# Sch_mcu_brd_mcu.net
KiCad netlist of a schematic drawn in Altium Designer
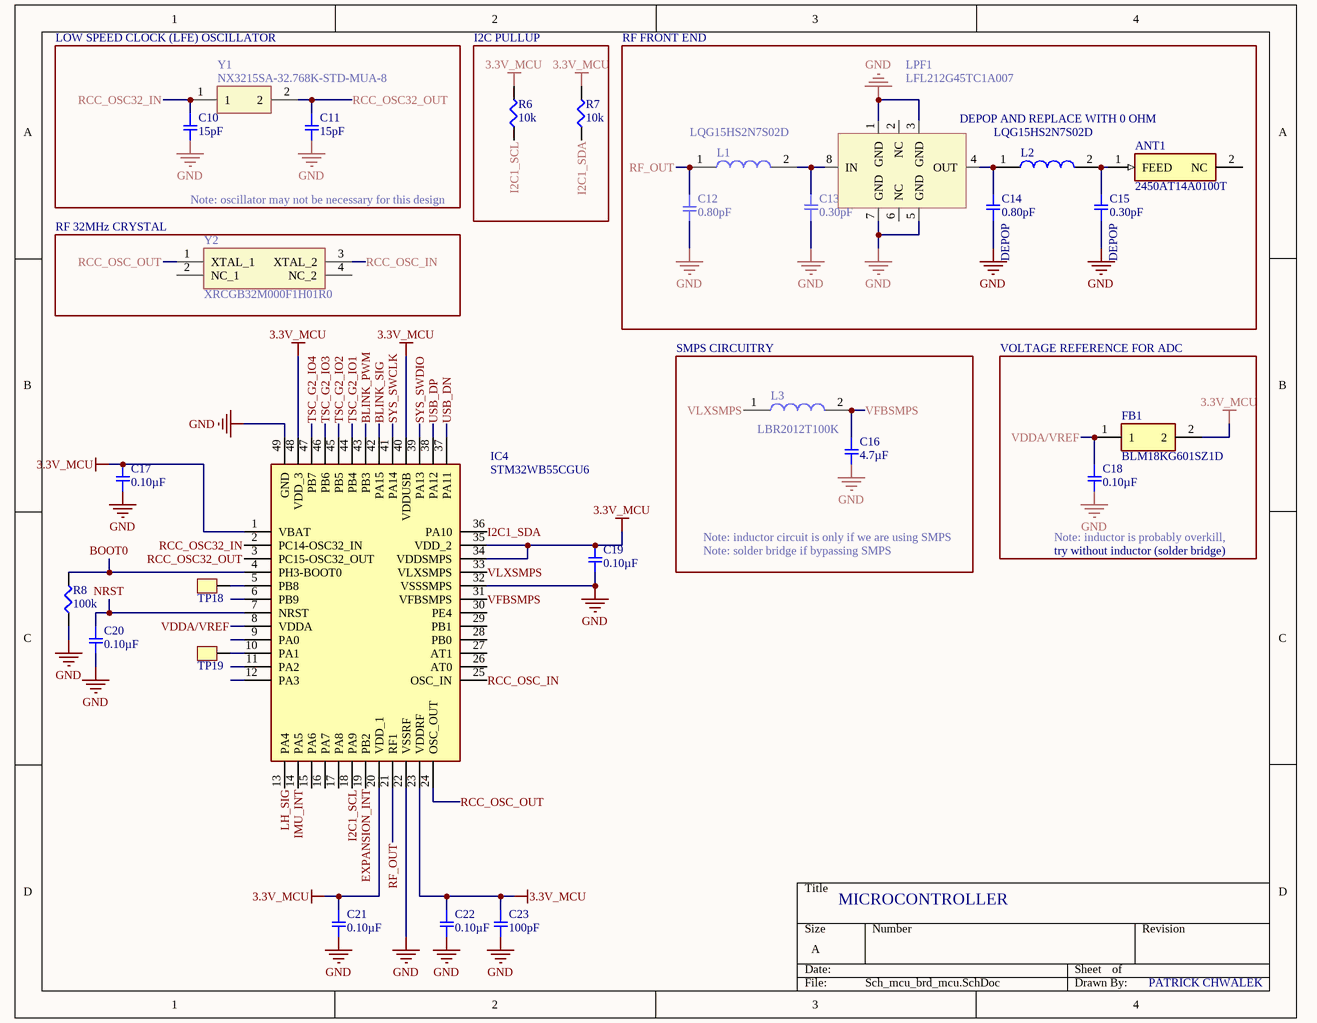
[diagram p0: Sch_mcu_brd_mcu.SchDoc]

(export (version "E")
  (design (tool "Eeschema 10.0.6"))
  (components
    (comp (ref "ANT1")
      (value "2450AT14A0100T")
      (footprint "SamacSys:ANTC1608X40N")
      (description "Antenna")
      (fields (field (name "MOUSER PART NUMBER") "609-2450AT14A0100T"))
      (libsource (lib "SamacSys") (part "2450AT14A0100T"))
    )
    (comp (ref "C10")
      (value "15pF")
      (footprint "SMD-0402C")
      (description "CAP CER 15PF 50V NP0 0402")
      (fields
        (field (name "DIGI-KEY PART NUMBER") "490-11147-1-ND")
        (field (name "PART NUMBER") "GCM1555C1H150JA16D")
      )
      (libsource (lib "capacitor_murata_0402") (part "GCM1555C1H150JA16D"))
    )
    (comp (ref "C11")
      (value "15pF")
      (footprint "SMD-0402C")
      (description "CAP CER 15PF 50V NP0 0402")
      (fields
        (field (name "DIGI-KEY PART NUMBER") "490-11147-1-ND")
        (field (name "PART NUMBER") "GCM1555C1H150JA16D")
      )
      (libsource (lib "capacitor_murata_0402") (part "GCM1555C1H150JA16D"))
    )
    (comp (ref "C12")
      (value "0.80pF")
      (footprint "SMD-0402C")
      (description "CAP CER 0.8PF 50V NP0 0402")
      (fields
        (field (name "DIGI-KEY PART NUMBER") "490-6269-1-ND")
        (field (name "PART NUMBER") "GRM1555C1HR80BA01D")
      )
      (libsource (lib "capacitor_murata_0402") (part "GRM1555C1HR80BA01D"))
    )
    (comp (ref "C13")
      (value "0.30pF")
      (footprint "SMD-0402C")
      (description "CAP CER 0.3PF 50V NP0 0402")
      (fields
        (field (name "DIGI-KEY PART NUMBER") "490-6261-1-ND")
        (field (name "PART NUMBER") "GRM1555C1HR30WA01D")
      )
      (libsource (lib "capacitor_murata_0402") (part "GRM1555C1HR30WA01D"))
    )
    (comp (ref "C14")
      (value "0.80pF")
      (footprint "SMD-0402C")
      (description "CAP CER 0.8PF 50V NP0 0402")
      (fields
        (field (name "DIGI-KEY PART NUMBER") "490-6269-1-ND")
        (field (name "PART NUMBER") "GRM1555C1HR80BA01D")
      )
      (libsource (lib "capacitor_murata_0402") (part "GRM1555C1HR80BA01D"))
    )
    (comp (ref "C15")
      (value "0.30pF")
      (footprint "SMD-0402C")
      (description "CAP CER 0.3PF 50V NP0 0402")
      (fields
        (field (name "DIGI-KEY PART NUMBER") "490-6261-1-ND")
        (field (name "PART NUMBER") "GRM1555C1HR30WA01D")
      )
      (libsource (lib "capacitor_murata_0402") (part "GRM1555C1HR30WA01D"))
    )
    (comp (ref "C16")
      (value "4.7µF")
      (footprint "SMD-0402C")
      (description "CAP CER 4.7UF 4V X5R 0402")
      (fields
        (field (name "DIGI-KEY PART NUMBER") "490-13231-1-ND")
        (field (name "PART NUMBER") "GRM153R60G475ME15D")
      )
      (libsource (lib "capacitor_murata_0402") (part "GRM153R60G475ME15D"))
    )
    (comp (ref "C17")
      (value "0.10µF")
      (footprint "SMD-0402C")
      (description "CAP CER 0.1UF 16V X7R 0402")
      (fields
        (field (name "DIGI-KEY PART NUMBER") "490-4759-1-ND")
        (field (name "PART NUMBER") "GCM155R71C104KA55D")
      )
      (libsource (lib "capacitor_murata_0402") (part "GCM155R71C104KA55D"))
    )
    (comp (ref "C18")
      (value "0.10µF")
      (footprint "SMD-0402C")
      (description "CAP CER 0.1UF 16V X7R 0402")
      (fields
        (field (name "DIGI-KEY PART NUMBER") "490-4759-1-ND")
        (field (name "PART NUMBER") "GCM155R71C104KA55D")
      )
      (libsource (lib "capacitor_murata_0402") (part "GCM155R71C104KA55D"))
    )
    (comp (ref "C19")
      (value "0.10µF")
      (footprint "SMD-0402C")
      (description "CAP CER 0.1UF 16V X7R 0402")
      (fields
        (field (name "DIGI-KEY PART NUMBER") "490-4759-1-ND")
        (field (name "PART NUMBER") "GCM155R71C104KA55D")
      )
      (libsource (lib "capacitor_murata_0402") (part "GCM155R71C104KA55D"))
    )
    (comp (ref "C20")
      (value "0.10µF")
      (footprint "SMD-0402C")
      (description "CAP CER 0.1UF 16V X7R 0402")
      (fields
        (field (name "DIGI-KEY PART NUMBER") "490-4759-1-ND")
        (field (name "PART NUMBER") "GCM155R71C104KA55D")
      )
      (libsource (lib "capacitor_murata_0402") (part "GCM155R71C104KA55D"))
    )
    (comp (ref "C21")
      (value "0.10µF")
      (footprint "SMD-0402C")
      (description "CAP CER 0.1UF 16V X7R 0402")
      (fields
        (field (name "DIGI-KEY PART NUMBER") "490-4759-1-ND")
        (field (name "PART NUMBER") "GCM155R71C104KA55D")
      )
      (libsource (lib "capacitor_murata_0402") (part "GCM155R71C104KA55D"))
    )
    (comp (ref "C22")
      (value "0.10µF")
      (footprint "SMD-0402C")
      (description "CAP CER 0.1UF 16V X7R 0402")
      (fields
        (field (name "DIGI-KEY PART NUMBER") "490-4759-1-ND")
        (field (name "PART NUMBER") "GCM155R71C104KA55D")
      )
      (libsource (lib "capacitor_murata_0402") (part "GCM155R71C104KA55D"))
    )
    (comp (ref "C23")
      (value "100pF")
      (footprint "SMD-0402C")
      (description "CAP CER 100PF 50V NP0 0402")
      (fields
        (field (name "DIGI-KEY PART NUMBER") "490-10669-1-ND")
        (field (name "PART NUMBER") "GCM1555C1H101JA16D")
      )
      (libsource (lib "capacitor_murata_0402") (part "GCM1555C1H101JA16D"))
    )
    (comp (ref "FB1")
      (value "BLM18KG601SZ1D")
      (footprint "SamacSys:BEADC1608X95N")
      (description "Ferrite Bead")
      (fields (field (name "MOUSER PART NUMBER") "81-BLM18KG601SZ1D"))
      (libsource (lib "*") (part "BLM18KG601SZ1D"))
    )
    (comp (ref "IC4")
      (value "STM32WB55CGU6")
      (footprint "SamacSys:QFN50P700X700X65-49N-D")
      (description "Integrated Circuit")
      (fields (field (name "MOUSER PART NUMBER") "511-STM32WB55CGU6"))
      (libsource (lib "SamacSys") (part "STM32WB55CGU6"))
    )
    (comp (ref "L1")
      (value "LQG15HS2N7S02D")
      (footprint "SamacSys:INDC1005X55N")
      (description "Inductor")
      (libsource (lib "SamacSys") (part "LQG15HS2N7S02D"))
    )
    (comp (ref "L2")
      (value "LQG15HS2N7S02D")
      (footprint "SamacSys:INDC1005X55N")
      (description "Inductor")
      (libsource (lib "SamacSys") (part "LQG15HS2N7S02D"))
    )
    (comp (ref "L3")
      (value "LBR2012T100K")
      (footprint "SamacSys:INDC2012X145N")
      (description "Inductor")
      (fields (field (name "MOUSER PART NUMBER") "963-LBR2012T100K"))
      (libsource (lib "SamacSys") (part "LBR2012T100K"))
    )
    (comp (ref "LPF1")
      (value "LFL212G45TC1A007")
      (footprint "custom_footprints:LFL212G45TC1A007")
      (libsource (lib "SamacSys") (part "LFL212G45TC1A007"))
    )
    (comp (ref "R6")
      (value "10k")
      (footprint "SMD-0402-RES")
      (description "RES SMD 10K OHM 5% 1/10W 0402")
      (fields (field (name "PART NUMBER") "ERJ-2GEJ103X") (field (name "DIGI-KEY PART NUMBER") "P10KJCT-ND"))
      (libsource (lib "Panasonic_ERJ_0402") (part "ERJ-2GEJ103X"))
    )
    (comp (ref "R7")
      (value "10k")
      (footprint "SMD-0402-RES")
      (description "RES SMD 10K OHM 5% 1/10W 0402")
      (fields (field (name "PART NUMBER") "ERJ-2GEJ103X") (field (name "DIGI-KEY PART NUMBER") "P10KJCT-ND"))
      (libsource (lib "Panasonic_ERJ_0402") (part "ERJ-2GEJ103X"))
    )
    (comp (ref "R8")
      (value "100k")
      (footprint "SMD-0402-RES")
      (description "RES SMD 100K OHM 1% 1/10W 0402")
      (fields
        (field (name "PART NUMBER") "ERJ-2RKF1003X")
        (field (name "DIGI-KEY PART NUMBER") "P100KLCT-ND")
      )
      (libsource (lib "Panasonic_ERJ_0402") (part "ERJ-2RKF1003X"))
    )
    (comp (ref "TP18")
      (value "TestPoint")
      (footprint "TestPoint_0.4mm")
      (libsource (lib "schematic_components") (part "TestPoint"))
    )
    (comp (ref "TP19")
      (value "TestPoint")
      (footprint "TestPoint_0.4mm")
      (libsource (lib "schematic_components") (part "TestPoint"))
    )
    (comp (ref "Y1")
      (value "NX3215SA-32.768K-STD-MUA-8")
      (footprint "SamacSys:NX3215SA")
      (description "Crystal or Oscillator")
      (fields (field (name "MOUSER PART NUMBER") "344-NX3215SA32768K8"))
      (libsource (lib "SamacSys") (part "NX3215SA-32.768K-STD-MUA-8"))
    )
    (comp (ref "Y2")
      (value "XRCGB32M000F1H01R0")
      (footprint "SamacSys:XRCGB32M000F1H01R0")
      (description "Crystal or Oscillator")
      (fields (field (name "MOUSER PART NUMBER") "81-XRCGB32M000F1H01R"))
      (libsource (lib "SamacSys") (part "XRCGB32M000F1H01R0"))
    )
  )
  (nets
    (net (code "1") (name "/BLINK_PWM") (class "Default")
      (node (ref "IC4") (pin "43") (pinfunction "PB3_43") (pintype "passive"))
    )
    (net (code "2") (name "/BLINK_SIG") (class "Default")
      (node (ref "IC4") (pin "42") (pinfunction "PA15_42") (pintype "passive"))
    )
    (net (code "3") (name "/BOOT0") (class "Default")
      (node (ref "IC4") (pin "4") (pinfunction "PH3-BOOT0_4") (pintype "passive"))
      (node (ref "R8") (pin "2") (pinfunction "2_2") (pintype "passive"))
    )
    (net (code "4") (name "/EXPANSION_INT") (class "Default")
      (node (ref "IC4") (pin "19") (pinfunction "PB2_19") (pintype "passive"))
    )
    (net (code "5") (name "/I2C1_SCL") (class "Default")
      (node (ref "IC4") (pin "18") (pinfunction "PA9_18") (pintype "passive"))
      (node (ref "R6") (pin "1") (pinfunction "1_1") (pintype "passive"))
    )
    (net (code "6") (name "/I2C1_SDA") (class "Default")
      (node (ref "IC4") (pin "36") (pinfunction "PA10_36") (pintype "passive"))
      (node (ref "R7") (pin "1") (pinfunction "1_1") (pintype "passive"))
    )
    (net (code "7") (name "/IMU_INT") (class "Default")
      (node (ref "IC4") (pin "14") (pinfunction "PA5_14") (pintype "passive"))
    )
    (net (code "8") (name "/LH_SIG") (class "Default")
      (node (ref "IC4") (pin "13") (pinfunction "PA4_13") (pintype "passive"))
    )
    (net (code "9") (name "/NRST") (class "Default")
      (node (ref "C20") (pin "1") (pinfunction "1_1") (pintype "passive"))
      (node (ref "IC4") (pin "7") (pinfunction "NRST_7") (pintype "passive"))
    )
    (net (code "10") (name "/RCC_OSC32_IN") (class "Default")
      (node (ref "C10") (pin "1") (pinfunction "1_1") (pintype "passive"))
      (node (ref "IC4") (pin "2") (pinfunction "PC14-OSC32_IN_2") (pintype "passive"))
      (node (ref "Y1") (pin "1") (pinfunction "1_1") (pintype "passive"))
    )
    (net (code "11") (name "/RCC_OSC32_OUT") (class "Default")
      (node (ref "C11") (pin "1") (pinfunction "1_1") (pintype "passive"))
      (node (ref "IC4") (pin "3") (pinfunction "PC15-OSC32_OUT_3") (pintype "passive"))
      (node (ref "Y1") (pin "2") (pinfunction "2_2") (pintype "passive"))
    )
    (net (code "12") (name "/RCC_OSC_IN") (class "Default")
      (node (ref "IC4") (pin "25") (pinfunction "OSC_IN_25") (pintype "passive"))
      (node (ref "Y2") (pin "3") (pinfunction "XTAL_2_3") (pintype "passive"))
    )
    (net (code "13") (name "/RCC_OSC_OUT") (class "Default")
      (node (ref "IC4") (pin "24") (pinfunction "OSC_OUT_24") (pintype "passive"))
      (node (ref "Y2") (pin "1") (pinfunction "XTAL_1_1") (pintype "passive"))
    )
    (net (code "14") (name "/RF_OUT") (class "Default")
      (node (ref "C12") (pin "1") (pinfunction "1_1") (pintype "passive"))
      (node (ref "IC4") (pin "21") (pinfunction "RF1_21") (pintype "passive"))
      (node (ref "L1") (pin "1") (pinfunction "1_1") (pintype "passive"))
    )
    (net (code "15") (name "/SYS_SWCLK") (class "Default")
      (node (ref "IC4") (pin "41") (pinfunction "PA14_41") (pintype "passive"))
    )
    (net (code "16") (name "/SYS_SWDIO") (class "Default")
      (node (ref "IC4") (pin "39") (pinfunction "PA13_39") (pintype "passive"))
    )
    (net (code "17") (name "/TSC_G2_IO1") (class "Default")
      (node (ref "IC4") (pin "44") (pinfunction "PB4_44") (pintype "passive"))
    )
    (net (code "18") (name "/TSC_G2_IO2") (class "Default")
      (node (ref "IC4") (pin "45") (pinfunction "PB5_45") (pintype "passive"))
    )
    (net (code "19") (name "/TSC_G2_IO3") (class "Default")
      (node (ref "IC4") (pin "46") (pinfunction "PB6_46") (pintype "passive"))
    )
    (net (code "20") (name "/TSC_G2_IO4") (class "Default")
      (node (ref "IC4") (pin "47") (pinfunction "PB7_47") (pintype "passive"))
    )
    (net (code "21") (name "/USB_DN") (class "Default")
      (node (ref "IC4") (pin "37") (pinfunction "PA11_37") (pintype "passive"))
    )
    (net (code "22") (name "/USB_DP") (class "Default")
      (node (ref "IC4") (pin "38") (pinfunction "PA12_38") (pintype "passive"))
    )
    (net (code "23") (name "/VDDA{slash}VREF") (class "Default")
      (node (ref "C18") (pin "1") (pinfunction "1_1") (pintype "passive"))
      (node (ref "FB1") (pin "1") (pinfunction "1_1") (pintype "passive"))
      (node (ref "IC4") (pin "8") (pinfunction "VDDA_8") (pintype "passive"))
    )
    (net (code "24") (name "/VFBSMPS") (class "Default")
      (node (ref "C16") (pin "1") (pinfunction "1_1") (pintype "passive"))
      (node (ref "IC4") (pin "31") (pinfunction "VFBSMPS_31") (pintype "passive"))
      (node (ref "L3") (pin "2") (pinfunction "2_2") (pintype "passive"))
    )
    (net (code "25") (name "/VLXSMPS") (class "Default")
      (node (ref "IC4") (pin "33") (pinfunction "VLXSMPS_33") (pintype "passive"))
      (node (ref "L3") (pin "1") (pinfunction "1_1") (pintype "passive"))
    )
    (net (code "26") (name "3.3V_MCU") (class "Default")
      (node (ref "C17") (pin "1") (pinfunction "1_1") (pintype "passive"))
      (node (ref "C19") (pin "1") (pinfunction "1_1") (pintype "passive"))
      (node (ref "C21") (pin "1") (pinfunction "1_1") (pintype "passive"))
      (node (ref "C22") (pin "1") (pinfunction "1_1") (pintype "passive"))
      (node (ref "C23") (pin "1") (pinfunction "1_1") (pintype "passive"))
      (node (ref "FB1") (pin "2") (pinfunction "2_2") (pintype "passive"))
      (node (ref "IC4") (pin "1") (pinfunction "VBAT_1") (pintype "passive"))
      (node (ref "IC4") (pin "20") (pinfunction "VDD_1_20") (pintype "passive"))
      (node (ref "IC4") (pin "23") (pinfunction "VDDRF_23") (pintype "passive"))
      (node (ref "IC4") (pin "34") (pinfunction "VDDSMPS_34") (pintype "passive"))
      (node (ref "IC4") (pin "35") (pinfunction "VDD_2_35") (pintype "passive"))
      (node (ref "IC4") (pin "40") (pinfunction "VDDUSB_40") (pintype "passive"))
      (node (ref "IC4") (pin "48") (pinfunction "VDD_3_48") (pintype "passive"))
      (node (ref "R6") (pin "2") (pinfunction "2_2") (pintype "passive"))
      (node (ref "R7") (pin "2") (pinfunction "2_2") (pintype "passive"))
    )
    (net (code "27") (name "GND") (class "Default")
      (node (ref "C10") (pin "2") (pinfunction "2_2") (pintype "passive"))
      (node (ref "C11") (pin "2") (pinfunction "2_2") (pintype "passive"))
      (node (ref "C12") (pin "2") (pinfunction "2_2") (pintype "passive"))
      (node (ref "C13") (pin "1") (pinfunction "1_1") (pintype "passive"))
      (node (ref "C14") (pin "1") (pinfunction "1_1") (pintype "passive"))
      (node (ref "C15") (pin "1") (pinfunction "1_1") (pintype "passive"))
      (node (ref "C16") (pin "2") (pinfunction "2_2") (pintype "passive"))
      (node (ref "C17") (pin "2") (pinfunction "2_2") (pintype "passive"))
      (node (ref "C18") (pin "2") (pinfunction "2_2") (pintype "passive"))
      (node (ref "C19") (pin "2") (pinfunction "2_2") (pintype "passive"))
      (node (ref "C20") (pin "2") (pinfunction "2_2") (pintype "passive"))
      (node (ref "C21") (pin "2") (pinfunction "2_2") (pintype "passive"))
      (node (ref "C22") (pin "2") (pinfunction "2_2") (pintype "passive"))
      (node (ref "C23") (pin "2") (pinfunction "2_2") (pintype "passive"))
      (node (ref "IC4") (pin "22") (pinfunction "VSSRF_22") (pintype "passive"))
      (node (ref "IC4") (pin "32") (pinfunction "VSSSMPS_32") (pintype "passive"))
      (node (ref "IC4") (pin "49") (pinfunction "GND_49") (pintype "passive"))
      (node (ref "LPF1") (pin "1") (pinfunction "GND_1") (pintype "passive"))
      (node (ref "LPF1") (pin "3") (pinfunction "GND_3") (pintype "passive"))
      (node (ref "LPF1") (pin "5") (pinfunction "GND_5") (pintype "passive"))
      (node (ref "LPF1") (pin "7") (pinfunction "GND_7") (pintype "passive"))
      (node (ref "R8") (pin "1") (pinfunction "1_1") (pintype "passive"))
    )
    (net (code "28") (name "Net-(ANT1-FEED)") (class "Default")
      (node (ref "ANT1") (pin "1") (pinfunction "FEED_1") (pintype "input"))
      (node (ref "C15") (pin "2") (pinfunction "2_2") (pintype "passive"))
      (node (ref "L2") (pin "2") (pinfunction "2_2") (pintype "passive"))
    )
    (net (code "29") (name "Net-(IC4-PA1)") (class "Default")
      (node (ref "IC4") (pin "10") (pinfunction "PA1_10") (pintype "passive"))
      (node (ref "TP19") (pin "1") (pinfunction "1_1") (pintype "passive"))
    )
    (net (code "30") (name "Net-(IC4-PB8)") (class "Default")
      (node (ref "IC4") (pin "5") (pinfunction "PB8_5") (pintype "passive"))
      (node (ref "TP18") (pin "1") (pinfunction "1_1") (pintype "passive"))
    )
    (net (code "31") (name "Net-(LPF1-IN)") (class "Default")
      (node (ref "C13") (pin "2") (pinfunction "2_2") (pintype "passive"))
      (node (ref "L1") (pin "2") (pinfunction "2_2") (pintype "passive"))
      (node (ref "LPF1") (pin "8") (pinfunction "IN_8") (pintype "passive"))
    )
    (net (code "32") (name "Net-(LPF1-OUT)") (class "Default")
      (node (ref "C14") (pin "2") (pinfunction "2_2") (pintype "passive"))
      (node (ref "L2") (pin "1") (pinfunction "1_1") (pintype "passive"))
      (node (ref "LPF1") (pin "4") (pinfunction "OUT_4") (pintype "passive"))
    )
    (net (code "33") (name "unconnected-(ANT1-NC-Pad2)") (class "Default")
      (node (ref "ANT1") (pin "2") (pinfunction "NC_2") (pintype "passive"))
    )
    (net (code "34") (name "unconnected-(IC4-AT0-Pad26)") (class "Default")
      (node (ref "IC4") (pin "26") (pinfunction "AT0_26") (pintype "passive"))
    )
    (net (code "35") (name "unconnected-(IC4-AT1-Pad27)") (class "Default")
      (node (ref "IC4") (pin "27") (pinfunction "AT1_27") (pintype "passive"))
    )
    (net (code "36") (name "unconnected-(IC4-PA0-Pad9)") (class "Default")
      (node (ref "IC4") (pin "9") (pinfunction "PA0_9") (pintype "passive"))
    )
    (net (code "37") (name "unconnected-(IC4-PA2-Pad11)") (class "Default")
      (node (ref "IC4") (pin "11") (pinfunction "PA2_11") (pintype "passive"))
    )
    (net (code "38") (name "unconnected-(IC4-PA3-Pad12)") (class "Default")
      (node (ref "IC4") (pin "12") (pinfunction "PA3_12") (pintype "passive"))
    )
    (net (code "39") (name "unconnected-(IC4-PA6-Pad15)") (class "Default")
      (node (ref "IC4") (pin "15") (pinfunction "PA6_15") (pintype "passive"))
    )
    (net (code "40") (name "unconnected-(IC4-PA7-Pad16)") (class "Default")
      (node (ref "IC4") (pin "16") (pinfunction "PA7_16") (pintype "passive"))
    )
    (net (code "41") (name "unconnected-(IC4-PA8-Pad17)") (class "Default")
      (node (ref "IC4") (pin "17") (pinfunction "PA8_17") (pintype "passive"))
    )
    (net (code "42") (name "unconnected-(IC4-PB0-Pad28)") (class "Default")
      (node (ref "IC4") (pin "28") (pinfunction "PB0_28") (pintype "passive"))
    )
    (net (code "43") (name "unconnected-(IC4-PB1-Pad29)") (class "Default")
      (node (ref "IC4") (pin "29") (pinfunction "PB1_29") (pintype "passive"))
    )
    (net (code "44") (name "unconnected-(IC4-PB9-Pad6)") (class "Default")
      (node (ref "IC4") (pin "6") (pinfunction "PB9_6") (pintype "passive"))
    )
    (net (code "45") (name "unconnected-(IC4-PE4-Pad30)") (class "Default")
      (node (ref "IC4") (pin "30") (pinfunction "PE4_30") (pintype "passive"))
    )
    (net (code "46") (name "unconnected-(LPF1-NC-Pad2)") (class "Default")
      (node (ref "LPF1") (pin "2") (pinfunction "NC_2") (pintype "passive"))
    )
    (net (code "47") (name "unconnected-(LPF1-NC-Pad6)") (class "Default")
      (node (ref "LPF1") (pin "6") (pinfunction "NC_6") (pintype "passive"))
    )
    (net (code "48") (name "unconnected-(Y2-NC_1-Pad2)") (class "Default")
      (node (ref "Y2") (pin "2") (pinfunction "NC_1_2") (pintype "passive"))
    )
    (net (code "49") (name "unconnected-(Y2-NC_2-Pad4)") (class "Default")
      (node (ref "Y2") (pin "4") (pinfunction "NC_2_4") (pintype "passive"))
    )
  )
)
